# CAN.net
KiCad netlist of a schematic drawn in Altium Designer
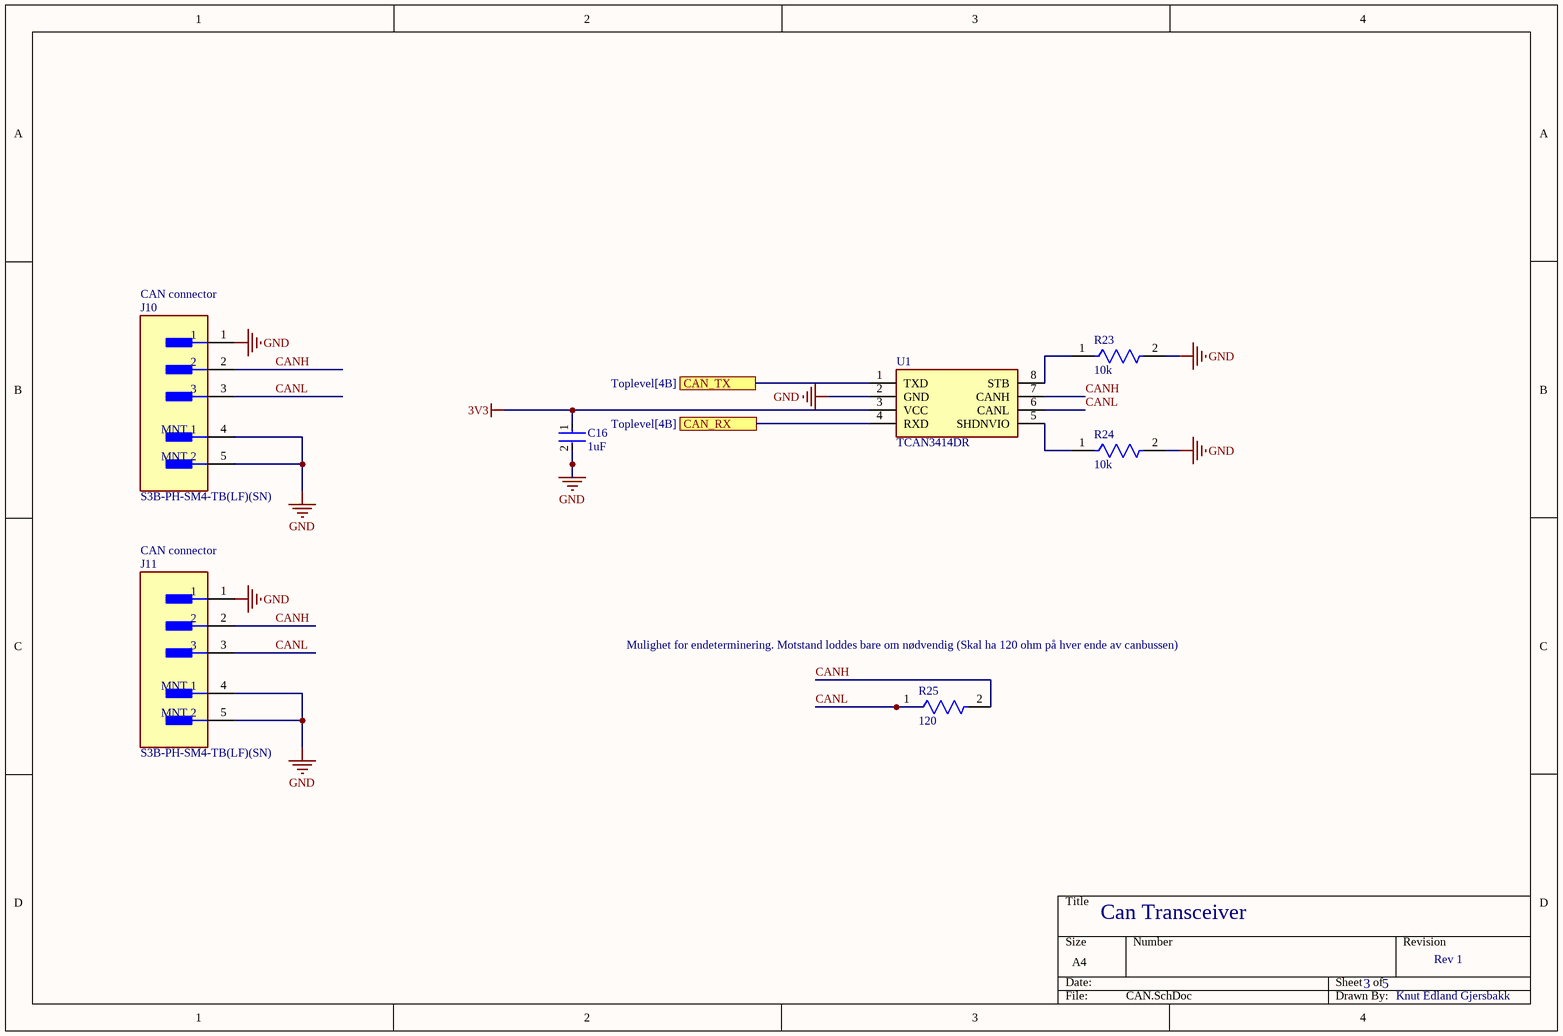
[diagram p0: CAN.SchDoc]

(export (version "E")
  (design (tool "Eeschema 10.0.6"))
  (components
    (comp (ref "C16")
      (value "1uF")
      (footprint "FP-CL10-IPC_C")
      (description "Cap Ceramic 1uF 16V X7R ±10% Pad SMD 0603 +125°C T/R\r\nCL10B105KO8NNNL")
      (fields (field (name "TOLERANCE") "10%"))
      (libsource (lib "Altium Content Vault") (part "b4654b650e69147ec39a6b967a45e02"))
    )
    (comp (ref "J10")
      (value "S3B-PH-SM4-TB(LF)(SN)")
      (footprint "FP-S3B-PH-SM4-TB_LF_SN-MFG")
      (description "Connector Header, PH Series, 3 Position, Side Entry, 2.00mm, Solder, Surface Mount, Natural.")
      (libsource (lib "UiS Aerospace") (part "38689d6f3df0f9b234c6ddcef280d85"))
    )
    (comp (ref "J11")
      (value "S3B-PH-SM4-TB(LF)(SN)")
      (footprint "FP-S3B-PH-SM4-TB_LF_SN-MFG")
      (description "Connector Header, PH Series, 3 Position, Side Entry, 2.00mm, Solder, Surface Mount, Natural.")
      (libsource (lib "UiS Aerospace") (part "38689d6f3df0f9b234c6ddcef280d85"))
    )
    (comp (ref "R23")
      (value "10k")
      (footprint "FP-RT0603-IPC_C")
      (description "RES SMD 10K OHM 1% 1/10W 0603\r\nRT0603FRE0710KL")
      (fields
        (field (name "MANUFACTURER") "Yageo")
        (field (name "OCTOPART") "https://octopart.com/rt0603fre0710kl-yageo-40009243")
      )
      (libsource (lib "Altium Content Vault") (part "1029c3af85768c4190bb7ad29bc67b5"))
    )
    (comp (ref "R24")
      (value "10k")
      (footprint "FP-RT0603-IPC_C")
      (description "RES SMD 10K OHM 1% 1/10W 0603\r\nRT0603FRE0710KL")
      (fields
        (field (name "MANUFACTURER") "Yageo")
        (field (name "OCTOPART") "https://octopart.com/rt0603fre0710kl-yageo-40009243")
      )
      (libsource (lib "Altium Content Vault") (part "1029c3af85768c4190bb7ad29bc67b5"))
    )
    (comp (ref "R25")
      (value "120")
      (footprint "FP-AF0603-IPC_C")
      (description "Anti-Sulfurated Chip Resistors Automotive Grade 120Ω 1% 100ppm/°C 0603 AF0603FR-07120RL")
      (fields (field (name "TOLERANCE") "1%"))
      (libsource (lib "Altium Content Vault") (part "1029c3af85768c4190bb7ad29bc67b5"))
    )
    (comp (ref "U1")
      (value "TCAN3414DR")
      (footprint "SamacSys:SOIC127P600X175-8N")
      (description "Integrated Circuit")
      (fields (field (name "MOUSER PART NUMBER") "595-TCAN3414DR"))
      (libsource (lib "*") (part "TCAN3414DR"))
    )
  )
  (nets
    (net (code "2") (name "/CANH") (class "Default")
      (node (ref "J10") (pin "2") (pinfunction "2_2") (pintype "passive"))
      (node (ref "J11") (pin "2") (pinfunction "2_2") (pintype "passive"))
      (node (ref "R25") (pin "2") (pinfunction "2_2") (pintype "passive"))
      (node (ref "U1") (pin "7") (pinfunction "CANH_7") (pintype "passive"))
    )
    (net (code "3") (name "/CANL") (class "Default")
      (node (ref "J10") (pin "3") (pinfunction "3_3") (pintype "passive"))
      (node (ref "J11") (pin "3") (pinfunction "3_3") (pintype "passive"))
      (node (ref "R25") (pin "1") (pinfunction "1_1") (pintype "passive"))
      (node (ref "U1") (pin "6") (pinfunction "CANL_6") (pintype "passive"))
    )
    (net (code "4") (name "/CAN_RX") (class "Default")
      (node (ref "U1") (pin "4") (pinfunction "RXD_4") (pintype "passive"))
    )
    (net (code "5") (name "/CAN_TX") (class "Default")
      (node (ref "U1") (pin "1") (pinfunction "TXD_1") (pintype "passive"))
    )
    (net (code "6") (name "3V3") (class "Default")
      (node (ref "C16") (pin "1") (pinfunction "1_1") (pintype "passive"))
      (node (ref "U1") (pin "3") (pinfunction "VCC_3") (pintype "passive"))
    )
    (net (code "7") (name "GND") (class "Default")
      (node (ref "C16") (pin "2") (pinfunction "2_2") (pintype "passive"))
      (node (ref "J10") (pin "1") (pinfunction "1_1") (pintype "passive"))
      (node (ref "J10") (pin "4") (pinfunction "MNT_1_4") (pintype "passive"))
      (node (ref "J10") (pin "5") (pinfunction "MNT_2_5") (pintype "passive"))
      (node (ref "J11") (pin "1") (pinfunction "1_1") (pintype "passive"))
      (node (ref "J11") (pin "4") (pinfunction "MNT_1_4") (pintype "passive"))
      (node (ref "J11") (pin "5") (pinfunction "MNT_2_5") (pintype "passive"))
      (node (ref "R23") (pin "2") (pinfunction "2_2") (pintype "passive"))
      (node (ref "R24") (pin "2") (pinfunction "2_2") (pintype "passive"))
      (node (ref "U1") (pin "2") (pinfunction "GND_2") (pintype "passive"))
    )
    (net (code "8") (name "Net-(U1-SHDNVIO)") (class "Default")
      (node (ref "R24") (pin "1") (pinfunction "1_1") (pintype "passive"))
      (node (ref "U1") (pin "5") (pinfunction "SHDNVIO_5") (pintype "passive"))
    )
    (net (code "9") (name "Net-(U1-STB)") (class "Default")
      (node (ref "R23") (pin "1") (pinfunction "1_1") (pintype "passive"))
      (node (ref "U1") (pin "8") (pinfunction "STB_8") (pintype "passive"))
    )
  )
)
